# controller.net
KiCad netlist of a schematic drawn in EAGLE
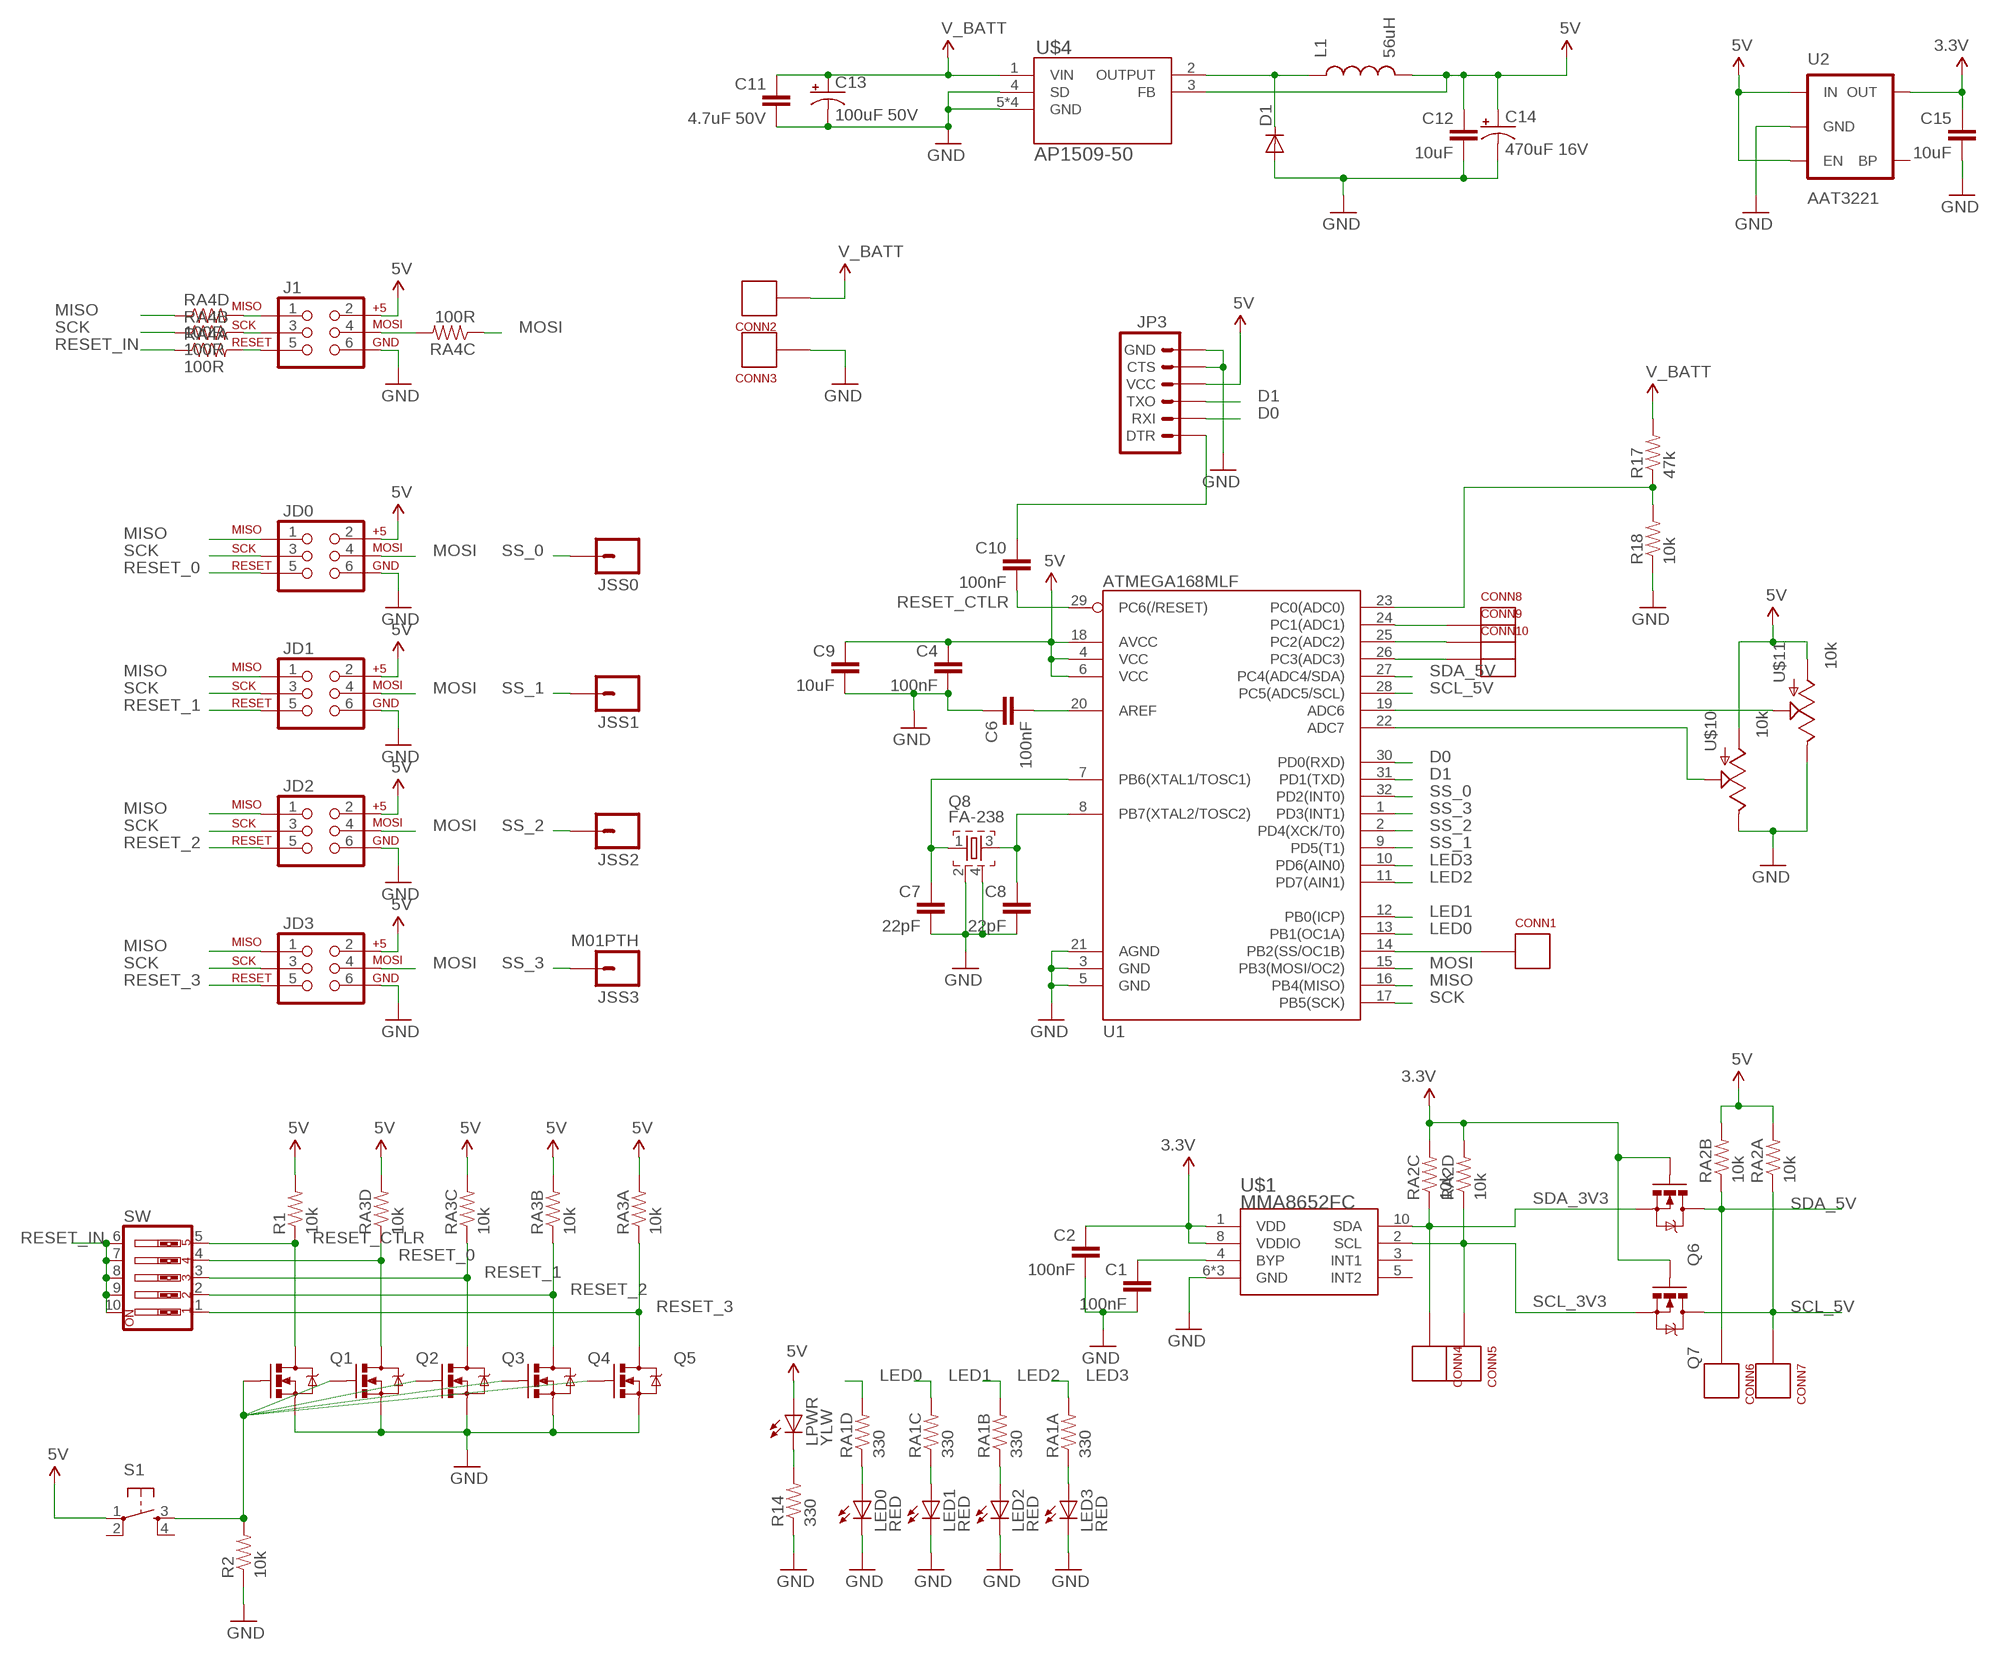
[diagram p0: schematic, sheet 1]

(export (version "E")
  (design (tool "Eeschema 10.0.6"))
  (components
    (comp (ref "C1")
      (value "100nF")
      (footprint "eagle-import:0402-CAP")
      (libsource (lib "eagle-import") (part "CAP0402-CAP"))
    )
    (comp (ref "C2")
      (value "100nF")
      (footprint "eagle-import:0402-CAP")
      (libsource (lib "eagle-import") (part "CAP0402-CAP"))
    )
    (comp (ref "C4")
      (value "100nF")
      (footprint "eagle-import:0402-CAP")
      (libsource (lib "eagle-import") (part "CAP0402-CAP"))
    )
    (comp (ref "C6")
      (value "100nF")
      (footprint "eagle-import:0402-CAP")
      (libsource (lib "eagle-import") (part "CAP0402-CAP"))
    )
    (comp (ref "C7")
      (value "22pF")
      (footprint "eagle-import:0402-CAP")
      (libsource (lib "eagle-import") (part "CAP0402-CAP"))
    )
    (comp (ref "C8")
      (value "22pF")
      (footprint "eagle-import:0402-CAP")
      (libsource (lib "eagle-import") (part "CAP0402-CAP"))
    )
    (comp (ref "C9")
      (value "10uF")
      (footprint "eagle-import:0805")
      (libsource (lib "eagle-import") (part "CAP0805"))
    )
    (comp (ref "C10")
      (value "100nF")
      (footprint "eagle-import:0402-CAP")
      (libsource (lib "eagle-import") (part "CAP0402-CAP"))
    )
    (comp (ref "C11")
      (value "4.7uF 50V")
      (footprint "eagle-import:0805")
      (libsource (lib "eagle-import") (part "CAP0805"))
    )
    (comp (ref "C12")
      (value "10uF")
      (footprint "eagle-import:0805")
      (libsource (lib "eagle-import") (part "CAP0805"))
    )
    (comp (ref "C13")
      (value "100uF 50V")
      (footprint "eagle-import:CAP-8-3.5")
      (libsource (lib "eagle-import") (part "CAP_POLPTH6"))
    )
    (comp (ref "C14")
      (value "470uF 16V")
      (footprint "eagle-import:CAP-8-3.5")
      (libsource (lib "eagle-import") (part "CAP_POLPTH6"))
    )
    (comp (ref "C15")
      (value "10uF")
      (footprint "eagle-import:0805")
      (libsource (lib "eagle-import") (part "CAP0805"))
    )
    (comp (ref "CONN1")
      (value "SS")
      (footprint "eagle-import:TESTPAD")
      (libsource (lib "eagle-import") (part "CONNECTOR"))
    )
    (comp (ref "CONN2")
      (value "CONNECTOR18AWG")
      (footprint "eagle-import:HOLE_18AWG")
      (libsource (lib "eagle-import") (part "CONNECTOR18AWG"))
    )
    (comp (ref "CONN3")
      (value "CONNECTOR18AWG")
      (footprint "eagle-import:HOLE_18AWG")
      (libsource (lib "eagle-import") (part "CONNECTOR18AWG"))
    )
    (comp (ref "CONN4")
      (value "D33")
      (footprint "eagle-import:TESTPAD")
      (libsource (lib "eagle-import") (part "CONNECTOR"))
    )
    (comp (ref "CONN5")
      (value "C33")
      (footprint "eagle-import:TESTPAD")
      (libsource (lib "eagle-import") (part "CONNECTOR"))
    )
    (comp (ref "CONN6")
      (value "D50")
      (footprint "eagle-import:TESTPAD")
      (libsource (lib "eagle-import") (part "CONNECTOR"))
    )
    (comp (ref "CONN7")
      (value "C50")
      (footprint "eagle-import:TESTPAD")
      (libsource (lib "eagle-import") (part "CONNECTOR"))
    )
    (comp (ref "CONN8")
      (value "PC1")
      (footprint "eagle-import:TESTPAD")
      (libsource (lib "eagle-import") (part "CONNECTOR"))
    )
    (comp (ref "CONN9")
      (value "PC2")
      (footprint "eagle-import:TESTPAD")
      (libsource (lib "eagle-import") (part "CONNECTOR"))
    )
    (comp (ref "CONN10")
      (value "PC3")
      (footprint "eagle-import:TESTPAD")
      (libsource (lib "eagle-import") (part "CONNECTOR"))
    )
    (comp (ref "D1")
      (value "DIODESOD123W")
      (footprint "eagle-import:SOD123W(NXP)")
      (libsource (lib "eagle-import") (part "DIODESOD123W"))
    )
    (comp (ref "J1")
      (value "AVR_SPI_PRG_6PTH")
      (footprint "eagle-import:2X3")
      (libsource (lib "eagle-import") (part "AVR_SPI_PRG_6PTH"))
    )
    (comp (ref "JD0")
      (value "AVR_SPI_PRG_6PTH")
      (footprint "eagle-import:2X3")
      (libsource (lib "eagle-import") (part "AVR_SPI_PRG_6PTH"))
    )
    (comp (ref "JD1")
      (value "AVR_SPI_PRG_6PTH")
      (footprint "eagle-import:2X3")
      (libsource (lib "eagle-import") (part "AVR_SPI_PRG_6PTH"))
    )
    (comp (ref "JD2")
      (value "AVR_SPI_PRG_6PTH")
      (footprint "eagle-import:2X3")
      (libsource (lib "eagle-import") (part "AVR_SPI_PRG_6PTH"))
    )
    (comp (ref "JD3")
      (value "AVR_SPI_PRG_6PTH")
      (footprint "eagle-import:2X3")
      (libsource (lib "eagle-import") (part "AVR_SPI_PRG_6PTH"))
    )
    (comp (ref "JP3")
      (value "ARDUINO_SERIAL_PROGRAMPTH")
      (footprint "eagle-import:1X06")
      (libsource (lib "eagle-import") (part "ARDUINO_SERIAL_PROGRAMPTH"))
    )
    (comp (ref "JSS0")
      (value "M01PTH")
      (footprint "eagle-import:1X01")
      (libsource (lib "eagle-import") (part "M01PTH"))
    )
    (comp (ref "JSS1")
      (value "M01PTH")
      (footprint "eagle-import:1X01")
      (libsource (lib "eagle-import") (part "M01PTH"))
    )
    (comp (ref "JSS2")
      (value "M01PTH")
      (footprint "eagle-import:1X01")
      (libsource (lib "eagle-import") (part "M01PTH"))
    )
    (comp (ref "JSS3")
      (value "M01PTH")
      (footprint "eagle-import:1X01")
      (libsource (lib "eagle-import") (part "M01PTH"))
    )
    (comp (ref "L1")
      (value "56uH")
      (footprint "eagle-import:1210")
      (libsource (lib "eagle-import") (part "INDUCTOR1210"))
    )
    (comp (ref "LED0")
      (value "RED")
      (footprint "eagle-import:LED-0603")
      (libsource (lib "eagle-import") (part "LED-RED0603"))
    )
    (comp (ref "LED1")
      (value "RED")
      (footprint "eagle-import:LED-0603")
      (libsource (lib "eagle-import") (part "LED-RED0603"))
    )
    (comp (ref "LED2")
      (value "RED")
      (footprint "eagle-import:LED-0603")
      (libsource (lib "eagle-import") (part "LED-RED0603"))
    )
    (comp (ref "LED3")
      (value "RED")
      (footprint "eagle-import:LED-0603")
      (libsource (lib "eagle-import") (part "LED-RED0603"))
    )
    (comp (ref "LPWR")
      (value "YLW")
      (footprint "eagle-import:LED-0603")
      (libsource (lib "eagle-import") (part "LED-RED0603"))
    )
    (comp (ref "Q1")
      (value "MOSFET-NCHANNELBSS123LT1G")
      (footprint "eagle-import:SOT23")
      (libsource (lib "eagle-import") (part "MOSFET-NCHANNELBSS123LT1G"))
    )
    (comp (ref "Q2")
      (value "MOSFET-NCHANNELBSS123LT1G")
      (footprint "eagle-import:SOT23")
      (libsource (lib "eagle-import") (part "MOSFET-NCHANNELBSS123LT1G"))
    )
    (comp (ref "Q3")
      (value "MOSFET-NCHANNELBSS123LT1G")
      (footprint "eagle-import:SOT23")
      (libsource (lib "eagle-import") (part "MOSFET-NCHANNELBSS123LT1G"))
    )
    (comp (ref "Q4")
      (value "MOSFET-NCHANNELBSS123LT1G")
      (footprint "eagle-import:SOT23")
      (libsource (lib "eagle-import") (part "MOSFET-NCHANNELBSS123LT1G"))
    )
    (comp (ref "Q5")
      (value "MOSFET-NCHANNELBSS123LT1G")
      (footprint "eagle-import:SOT23")
      (libsource (lib "eagle-import") (part "MOSFET-NCHANNELBSS123LT1G"))
    )
    (comp (ref "Q6")
      (value "MOSFET-NCHANNELBSS123LT1G")
      (footprint "eagle-import:SOT23")
      (libsource (lib "eagle-import") (part "MOSFET-NCHANNELBSS123LT1G"))
    )
    (comp (ref "Q7")
      (value "MOSFET-NCHANNELBSS123LT1G")
      (footprint "eagle-import:SOT23")
      (libsource (lib "eagle-import") (part "MOSFET-NCHANNELBSS123LT1G"))
    )
    (comp (ref "Q8")
      (value "FA-238")
      (footprint "eagle-import:FA-238")
      (libsource (lib "eagle-import") (part "FA-238"))
    )
    (comp (ref "R1")
      (value "10k")
      (footprint "eagle-import:0603-RES")
      (libsource (lib "eagle-import") (part "kmod_RESISTOR0603"))
    )
    (comp (ref "R2")
      (value "10k")
      (footprint "eagle-import:0603-RES")
      (libsource (lib "eagle-import") (part "kmod_RESISTOR0603"))
    )
    (comp (ref "R14")
      (value "330")
      (footprint "eagle-import:0603-RES")
      (libsource (lib "eagle-import") (part "RESISTOR0603"))
    )
    (comp (ref "R17")
      (value "47k")
      (footprint "eagle-import:0603-RES")
      (libsource (lib "eagle-import") (part "kmod_RESISTOR0603"))
    )
    (comp (ref "R18")
      (value "10k")
      (footprint "eagle-import:0603-RES")
      (libsource (lib "eagle-import") (part "kmod_RESISTOR0603"))
    )
    (comp (ref "RA1")
      (value "330")
      (footprint "eagle-import:0603-ARV")
      (libsource (lib "eagle-import") (part "RESISTOR_ARRAY0603_X4"))
    )
    (comp (ref "RA2")
      (value "10k")
      (footprint "eagle-import:0603-ARV")
      (libsource (lib "eagle-import") (part "RESISTOR_ARRAY0603_X4"))
    )
    (comp (ref "RA3")
      (value "10k")
      (footprint "eagle-import:0603-ARV")
      (libsource (lib "eagle-import") (part "RESISTOR_ARRAY0603_X4"))
    )
    (comp (ref "RA4")
      (value "100R")
      (footprint "eagle-import:0603-ARV")
      (libsource (lib "eagle-import") (part "RESISTOR_ARRAY0603_X4"))
    )
    (comp (ref "S1")
      (value "TAC_SWITCHPTH")
      (footprint "eagle-import:TACTILE-PTH")
      (libsource (lib "eagle-import") (part "TAC_SWITCHPTH"))
    )
    (comp (ref "SW")
      (value "SW_DIP-5")
      (footprint "eagle-import:DIPSWITCH-05")
      (libsource (lib "eagle-import") (part "SW_DIP-5"))
    )
    (comp (ref "U$1")
      (value "MMA8652FC")
      (footprint "eagle-import:DFN-10")
      (libsource (lib "eagle-import") (part "MMA8652FC"))
    )
    (comp (ref "U$4")
      (value "AP1509-50")
      (footprint "eagle-import:SO08")
      (libsource (lib "eagle-import") (part "AP1509"))
    )
    (comp (ref "U$10")
      (value "10k")
      (footprint "eagle-import:TRIM_POT")
      (libsource (lib "eagle-import") (part "POTTRIM"))
    )
    (comp (ref "U$11")
      (value "10k")
      (footprint "eagle-import:TRIM_POT")
      (libsource (lib "eagle-import") (part "POTTRIM"))
    )
    (comp (ref "U1")
      (value "ATMEGA168MLF")
      (footprint "eagle-import:MLF32")
      (libsource (lib "eagle-import") (part "ATMEGA168MLF"))
    )
    (comp (ref "U2")
      (value "AAT3221")
      (footprint "eagle-import:SOT23-5")
      (libsource (lib "eagle-import") (part "V_REG_LDOSMD"))
    )
  )
  (nets
    (net (code "1") (name "/D0") (class "Default")
      (node (ref "JP3") (pin "2") (pinfunction "RXI_2") (pintype "passive"))
      (node (ref "U1") (pin "30") (pinfunction "PD0(RXD)_30") (pintype "bidirectional"))
    )
    (net (code "2") (name "/D1") (class "Default")
      (node (ref "JP3") (pin "3") (pinfunction "TXO_3") (pintype "passive"))
      (node (ref "U1") (pin "31") (pinfunction "PD1(TXD)_31") (pintype "bidirectional"))
    )
    (net (code "3") (name "/LED0") (class "Default")
      (node (ref "RA1") (pin "5") (pinfunction "2_5") (pintype "passive"))
      (node (ref "U1") (pin "13") (pinfunction "PB1(OC1A)_13") (pintype "bidirectional"))
    )
    (net (code "4") (name "/LED1") (class "Default")
      (node (ref "RA1") (pin "6") (pinfunction "2_6") (pintype "passive"))
      (node (ref "U1") (pin "12") (pinfunction "PB0(ICP)_12") (pintype "bidirectional"))
    )
    (net (code "5") (name "/LED2") (class "Default")
      (node (ref "RA1") (pin "7") (pinfunction "2_7") (pintype "passive"))
      (node (ref "U1") (pin "11") (pinfunction "PD7(AIN1)_11") (pintype "bidirectional"))
    )
    (net (code "6") (name "/LED3") (class "Default")
      (node (ref "RA1") (pin "8") (pinfunction "2_8") (pintype "passive"))
      (node (ref "U1") (pin "10") (pinfunction "PD6(AIN0)_10") (pintype "bidirectional"))
    )
    (net (code "7") (name "/MISO") (class "Default")
      (node (ref "JD0") (pin "1") (pinfunction "1_1") (pintype "passive"))
      (node (ref "JD1") (pin "1") (pinfunction "1_1") (pintype "passive"))
      (node (ref "JD2") (pin "1") (pinfunction "1_1") (pintype "passive"))
      (node (ref "JD3") (pin "1") (pinfunction "1_1") (pintype "passive"))
      (node (ref "RA4") (pin "4") (pinfunction "1_4") (pintype "passive"))
      (node (ref "U1") (pin "16") (pinfunction "PB4(MISO)_16") (pintype "bidirectional"))
    )
    (net (code "8") (name "/MOSI") (class "Default")
      (node (ref "JD0") (pin "4") (pinfunction "4_4") (pintype "passive"))
      (node (ref "JD1") (pin "4") (pinfunction "4_4") (pintype "passive"))
      (node (ref "JD2") (pin "4") (pinfunction "4_4") (pintype "passive"))
      (node (ref "JD3") (pin "4") (pinfunction "4_4") (pintype "passive"))
      (node (ref "RA4") (pin "3") (pinfunction "1_3") (pintype "passive"))
      (node (ref "U1") (pin "15") (pinfunction "PB3(MOSI/OC2)_15") (pintype "bidirectional"))
    )
    (net (code "9") (name "/RESET_0") (class "Default")
      (node (ref "JD0") (pin "5") (pinfunction "5_5") (pintype "passive"))
      (node (ref "Q2") (pin "3") (pinfunction "D_3") (pintype "passive"))
      (node (ref "RA3") (pin "4") (pinfunction "1_4") (pintype "passive"))
      (node (ref "SW") (pin "4") (pinfunction "4_4") (pintype "passive"))
    )
    (net (code "10") (name "/RESET_1") (class "Default")
      (node (ref "JD1") (pin "5") (pinfunction "5_5") (pintype "passive"))
      (node (ref "Q3") (pin "3") (pinfunction "D_3") (pintype "passive"))
      (node (ref "RA3") (pin "3") (pinfunction "1_3") (pintype "passive"))
      (node (ref "SW") (pin "3") (pinfunction "3_3") (pintype "passive"))
    )
    (net (code "11") (name "/RESET_2") (class "Default")
      (node (ref "JD2") (pin "5") (pinfunction "5_5") (pintype "passive"))
      (node (ref "Q4") (pin "3") (pinfunction "D_3") (pintype "passive"))
      (node (ref "RA3") (pin "2") (pinfunction "1_2") (pintype "passive"))
      (node (ref "SW") (pin "2") (pinfunction "2_2") (pintype "passive"))
    )
    (net (code "12") (name "/RESET_3") (class "Default")
      (node (ref "JD3") (pin "5") (pinfunction "5_5") (pintype "passive"))
      (node (ref "Q5") (pin "3") (pinfunction "D_3") (pintype "passive"))
      (node (ref "RA3") (pin "1") (pinfunction "1_1") (pintype "passive"))
      (node (ref "SW") (pin "1") (pinfunction "1_1") (pintype "passive"))
    )
    (net (code "13") (name "/RESET_CTLR") (class "Default")
      (node (ref "C10") (pin "2") (pinfunction "2_2") (pintype "passive"))
      (node (ref "Q1") (pin "3") (pinfunction "D_3") (pintype "passive"))
      (node (ref "R1") (pin "1") (pinfunction "1_1") (pintype "passive"))
      (node (ref "SW") (pin "5") (pinfunction "5_5") (pintype "passive"))
      (node (ref "U1") (pin "29") (pinfunction "PC6(/RESET)_29") (pintype "bidirectional"))
    )
    (net (code "14") (name "/RESET_IN") (class "Default")
      (node (ref "RA4") (pin "1") (pinfunction "1_1") (pintype "passive"))
      (node (ref "SW") (pin "10") (pinfunction "16_10") (pintype "passive"))
      (node (ref "SW") (pin "6") (pinfunction "12_6") (pintype "passive"))
      (node (ref "SW") (pin "7") (pinfunction "13_7") (pintype "passive"))
      (node (ref "SW") (pin "8") (pinfunction "14_8") (pintype "passive"))
      (node (ref "SW") (pin "9") (pinfunction "15_9") (pintype "passive"))
    )
    (net (code "15") (name "/SCK") (class "Default")
      (node (ref "JD0") (pin "3") (pinfunction "3_3") (pintype "passive"))
      (node (ref "JD1") (pin "3") (pinfunction "3_3") (pintype "passive"))
      (node (ref "JD2") (pin "3") (pinfunction "3_3") (pintype "passive"))
      (node (ref "JD3") (pin "3") (pinfunction "3_3") (pintype "passive"))
      (node (ref "RA4") (pin "2") (pinfunction "1_2") (pintype "passive"))
      (node (ref "U1") (pin "17") (pinfunction "PB5(SCK)_17") (pintype "bidirectional"))
    )
    (net (code "16") (name "/SCL_3V3") (class "Default")
      (node (ref "CONN5") (pin "P") (pinfunction "P_P") (pintype "bidirectional"))
      (node (ref "Q7") (pin "2") (pinfunction "S_2") (pintype "passive"))
      (node (ref "RA2") (pin "4") (pinfunction "1_4") (pintype "passive"))
      (node (ref "U$1") (pin "2") (pinfunction "SCL_2") (pintype "bidirectional"))
    )
    (net (code "17") (name "/SCL_5V") (class "Default")
      (node (ref "CONN7") (pin "P") (pinfunction "P_P") (pintype "bidirectional"))
      (node (ref "Q7") (pin "3") (pinfunction "D_3") (pintype "passive"))
      (node (ref "RA2") (pin "1") (pinfunction "1_1") (pintype "passive"))
      (node (ref "U1") (pin "28") (pinfunction "PC5(ADC5/SCL)_28") (pintype "bidirectional"))
    )
    (net (code "18") (name "/SDA_3V3") (class "Default")
      (node (ref "CONN4") (pin "P") (pinfunction "P_P") (pintype "bidirectional"))
      (node (ref "Q6") (pin "2") (pinfunction "S_2") (pintype "passive"))
      (node (ref "RA2") (pin "3") (pinfunction "1_3") (pintype "passive"))
      (node (ref "U$1") (pin "10") (pinfunction "SDA_10") (pintype "bidirectional"))
    )
    (net (code "19") (name "/SDA_5V") (class "Default")
      (node (ref "CONN6") (pin "P") (pinfunction "P_P") (pintype "bidirectional"))
      (node (ref "Q6") (pin "3") (pinfunction "D_3") (pintype "passive"))
      (node (ref "RA2") (pin "2") (pinfunction "1_2") (pintype "passive"))
      (node (ref "U1") (pin "27") (pinfunction "PC4(ADC4/SDA)_27") (pintype "bidirectional"))
    )
    (net (code "20") (name "/SS_0") (class "Default")
      (node (ref "JSS0") (pin "1") (pinfunction "1_1") (pintype "passive"))
      (node (ref "U1") (pin "32") (pinfunction "PD2(INT0)_32") (pintype "bidirectional"))
    )
    (net (code "21") (name "/SS_1") (class "Default")
      (node (ref "JSS1") (pin "1") (pinfunction "1_1") (pintype "passive"))
      (node (ref "U1") (pin "9") (pinfunction "PD5(T1)_9") (pintype "bidirectional"))
    )
    (net (code "22") (name "/SS_2") (class "Default")
      (node (ref "JSS2") (pin "1") (pinfunction "1_1") (pintype "passive"))
      (node (ref "U1") (pin "2") (pinfunction "PD4(XCK/T0)_2") (pintype "bidirectional"))
    )
    (net (code "23") (name "/SS_3") (class "Default")
      (node (ref "JSS3") (pin "1") (pinfunction "1_1") (pintype "passive"))
      (node (ref "U1") (pin "1") (pinfunction "PD3(INT1)_1") (pintype "bidirectional"))
    )
    (net (code "24") (name "3.3V") (class "Default")
      (node (ref "C15") (pin "1") (pinfunction "1_1") (pintype "passive"))
      (node (ref "C2") (pin "1") (pinfunction "1_1") (pintype "passive"))
      (node (ref "Q6") (pin "1") (pinfunction "G_1") (pintype "passive"))
      (node (ref "Q7") (pin "1") (pinfunction "G_1") (pintype "passive"))
      (node (ref "RA2") (pin "5") (pinfunction "2_5") (pintype "passive"))
      (node (ref "RA2") (pin "6") (pinfunction "2_6") (pintype "passive"))
      (node (ref "U$1") (pin "1") (pinfunction "VDD_1") (pintype "bidirectional"))
      (node (ref "U$1") (pin "8") (pinfunction "VDDIO_8") (pintype "bidirectional"))
      (node (ref "U2") (pin "5") (pinfunction "OUT_5") (pintype "passive"))
    )
    (net (code "25") (name "5V") (class "Default")
      (node (ref "C12") (pin "1") (pinfunction "1_1") (pintype "passive"))
      (node (ref "C14") (pin "1") (pinfunction "+_1") (pintype "passive"))
      (node (ref "C4") (pin "1") (pinfunction "1_1") (pintype "passive"))
      (node (ref "C9") (pin "1") (pinfunction "1_1") (pintype "passive"))
      (node (ref "J1") (pin "2") (pinfunction "2_2") (pintype "passive"))
      (node (ref "JD0") (pin "2") (pinfunction "2_2") (pintype "passive"))
      (node (ref "JD1") (pin "2") (pinfunction "2_2") (pintype "passive"))
      (node (ref "JD2") (pin "2") (pinfunction "2_2") (pintype "passive"))
      (node (ref "JD3") (pin "2") (pinfunction "2_2") (pintype "passive"))
      (node (ref "JP3") (pin "4") (pinfunction "VCC_4") (pintype "passive"))
      (node (ref "L1") (pin "2") (pinfunction "2_2") (pintype "passive"))
      (node (ref "LPWR") (pin "A") (pinfunction "A_A") (pintype "passive"))
      (node (ref "R1") (pin "2") (pinfunction "2_2") (pintype "passive"))
      (node (ref "RA2") (pin "7") (pinfunction "2_7") (pintype "passive"))
      (node (ref "RA2") (pin "8") (pinfunction "2_8") (pintype "passive"))
      (node (ref "RA3") (pin "5") (pinfunction "2_5") (pintype "passive"))
      (node (ref "RA3") (pin "6") (pinfunction "2_6") (pintype "passive"))
      (node (ref "RA3") (pin "7") (pinfunction "2_7") (pintype "passive"))
      (node (ref "RA3") (pin "8") (pinfunction "2_8") (pintype "passive"))
      (node (ref "S1") (pin "1") (pinfunction "1_1") (pintype "passive"))
      (node (ref "U$10") (pin "3") (pinfunction "A_3") (pintype "passive"))
      (node (ref "U$11") (pin "3") (pinfunction "A_3") (pintype "passive"))
      (node (ref "U$4") (pin "3") (pinfunction "FB_3") (pintype "bidirectional"))
      (node (ref "U1") (pin "18") (pinfunction "AVCC_18") (pintype "bidirectional"))
      (node (ref "U1") (pin "4") (pinfunction "VCC_4") (pintype "bidirectional"))
      (node (ref "U1") (pin "6") (pinfunction "VCC_6") (pintype "bidirectional"))
      (node (ref "U2") (pin "1") (pinfunction "IN_1") (pintype "input"))
      (node (ref "U2") (pin "3") (pinfunction "EN_3") (pintype "input"))
    )
    (net (code "26") (name "GND") (class "Default")
      (node (ref "C1") (pin "2") (pinfunction "2_2") (pintype "passive"))
      (node (ref "C11") (pin "2") (pinfunction "2_2") (pintype "passive"))
      (node (ref "C12") (pin "2") (pinfunction "2_2") (pintype "passive"))
      (node (ref "C13") (pin "2") (pinfunction "-_2") (pintype "passive"))
      (node (ref "C14") (pin "2") (pinfunction "-_2") (pintype "passive"))
      (node (ref "C15") (pin "2") (pinfunction "2_2") (pintype "passive"))
      (node (ref "C2") (pin "2") (pinfunction "2_2") (pintype "passive"))
      (node (ref "C4") (pin "2") (pinfunction "2_2") (pintype "passive"))
      (node (ref "C6") (pin "1") (pinfunction "1_1") (pintype "passive"))
      (node (ref "C7") (pin "2") (pinfunction "2_2") (pintype "passive"))
      (node (ref "C8") (pin "2") (pinfunction "2_2") (pintype "passive"))
      (node (ref "C9") (pin "2") (pinfunction "2_2") (pintype "passive"))
      (node (ref "CONN3") (pin "P$1") (pinfunction "P_P$1") (pintype "bidirectional"))
      (node (ref "D1") (pin "A") (pinfunction "A_A") (pintype "passive"))
      (node (ref "J1") (pin "6") (pinfunction "6_6") (pintype "passive"))
      (node (ref "JD0") (pin "6") (pinfunction "6_6") (pintype "passive"))
      (node (ref "JD1") (pin "6") (pinfunction "6_6") (pintype "passive"))
      (node (ref "JD2") (pin "6") (pinfunction "6_6") (pintype "passive"))
      (node (ref "JD3") (pin "6") (pinfunction "6_6") (pintype "passive"))
      (node (ref "JP3") (pin "5") (pinfunction "CTS_5") (pintype "passive"))
      (node (ref "JP3") (pin "6") (pinfunction "GND_6") (pintype "passive"))
      (node (ref "LED0") (pin "C") (pinfunction "C_C") (pintype "passive"))
      (node (ref "LED1") (pin "C") (pinfunction "C_C") (pintype "passive"))
      (node (ref "LED2") (pin "C") (pinfunction "C_C") (pintype "passive"))
      (node (ref "LED3") (pin "C") (pinfunction "C_C") (pintype "passive"))
      (node (ref "Q1") (pin "2") (pinfunction "S_2") (pintype "passive"))
      (node (ref "Q2") (pin "2") (pinfunction "S_2") (pintype "passive"))
      (node (ref "Q3") (pin "2") (pinfunction "S_2") (pintype "passive"))
      (node (ref "Q4") (pin "2") (pinfunction "S_2") (pintype "passive"))
      (node (ref "Q5") (pin "2") (pinfunction "S_2") (pintype "passive"))
      (node (ref "Q8") (pin "2") (pinfunction "2_2") (pintype "passive"))
      (node (ref "Q8") (pin "4") (pinfunction "4_4") (pintype "passive"))
      (node (ref "R14") (pin "1") (pinfunction "1_1") (pintype "passive"))
      (node (ref "R18") (pin "1") (pinfunction "1_1") (pintype "passive"))
      (node (ref "R2") (pin "1") (pinfunction "1_1") (pintype "passive"))
      (node (ref "U$1") (pin "6") (pinfunction "GND_6") (pintype "bidirectional"))
      (node (ref "U$1") (pin "7") (pinfunction "GND_7") (pintype "bidirectional"))
      (node (ref "U$1") (pin "9") (pinfunction "GND_9") (pintype "bidirectional"))
      (node (ref "U$10") (pin "2") (pinfunction "E_2") (pintype "passive"))
      (node (ref "U$11") (pin "2") (pinfunction "E_2") (pintype "passive"))
      (node (ref "U$4") (pin "4") (pinfunction "SD_4") (pintype "bidirectional"))
      (node (ref "U$4") (pin "5") (pinfunction "GND_5") (pintype "bidirectional"))
      (node (ref "U$4") (pin "6") (pinfunction "GND_6") (pintype "bidirectional"))
      (node (ref "U$4") (pin "7") (pinfunction "GND_7") (pintype "bidirectional"))
      (node (ref "U$4") (pin "8") (pinfunction "GND_8") (pintype "bidirectional"))
      (node (ref "U1") (pin "21") (pinfunction "AGND_21") (pintype "bidirectional"))
      (node (ref "U1") (pin "3") (pinfunction "GND_3") (pintype "bidirectional"))
      (node (ref "U1") (pin "5") (pinfunction "GND_5") (pintype "bidirectional"))
      (node (ref "U2") (pin "2") (pinfunction "GND_2") (pintype "input"))
    )
    (net (code "27") (name "Net-(JP3-DTR)") (class "Default")
      (node (ref "C10") (pin "1") (pinfunction "1_1") (pintype "passive"))
      (node (ref "JP3") (pin "1") (pinfunction "DTR_1") (pintype "passive"))
    )
    (net (code "28") (name "Net-(LED3-PadA)") (class "Default")
      (node (ref "LED3") (pin "A") (pinfunction "A_A") (pintype "passive"))
      (node (ref "RA1") (pin "1") (pinfunction "1_1") (pintype "passive"))
    )
    (net (code "29") (name "Net-(LPWR-PadC)") (class "Default")
      (node (ref "LPWR") (pin "C") (pinfunction "C_C") (pintype "passive"))
      (node (ref "R14") (pin "2") (pinfunction "2_2") (pintype "passive"))
    )
    (net (code "30") (name "Net-(Q1-G)") (class "Default")
      (node (ref "Q1") (pin "1") (pinfunction "G_1") (pintype "passive"))
      (node (ref "Q2") (pin "1") (pinfunction "G_1") (pintype "passive"))
      (node (ref "Q3") (pin "1") (pinfunction "G_1") (pintype "passive"))
      (node (ref "Q4") (pin "1") (pinfunction "G_1") (pintype "passive"))
      (node (ref "Q5") (pin "1") (pinfunction "G_1") (pintype "passive"))
      (node (ref "R2") (pin "2") (pinfunction "2_2") (pintype "passive"))
      (node (ref "S1") (pin "3") (pinfunction "3_3") (pintype "passive"))
    )
    (net (code "31") (name "Net-(RA1B-1)") (class "Default")
      (node (ref "LED2") (pin "A") (pinfunction "A_A") (pintype "passive"))
      (node (ref "RA1") (pin "2") (pinfunction "1_2") (pintype "passive"))
    )
    (net (code "32") (name "Net-(RA1C-1)") (class "Default")
      (node (ref "LED1") (pin "A") (pinfunction "A_A") (pintype "passive"))
      (node (ref "RA1") (pin "3") (pinfunction "1_3") (pintype "passive"))
    )
    (net (code "33") (name "Net-(RA1D-1)") (class "Default")
      (node (ref "LED0") (pin "A") (pinfunction "A_A") (pintype "passive"))
      (node (ref "RA1") (pin "4") (pinfunction "1_4") (pintype "passive"))
    )
    (net (code "34") (name "Net-(RA4A-2)") (class "Default")
      (node (ref "J1") (pin "5") (pinfunction "5_5") (pintype "passive"))
      (node (ref "RA4") (pin "8") (pinfunction "2_8") (pintype "passive"))
    )
    (net (code "35") (name "Net-(RA4B-2)") (class "Default")
      (node (ref "J1") (pin "3") (pinfunction "3_3") (pintype "passive"))
      (node (ref "RA4") (pin "7") (pinfunction "2_7") (pintype "passive"))
    )
    (net (code "36") (name "Net-(RA4C-2)") (class "Default")
      (node (ref "J1") (pin "4") (pinfunction "4_4") (pintype "passive"))
      (node (ref "RA4") (pin "6") (pinfunction "2_6") (pintype "passive"))
    )
    (net (code "37") (name "Net-(RA4D-2)") (class "Default")
      (node (ref "J1") (pin "1") (pinfunction "1_1") (pintype "passive"))
      (node (ref "RA4") (pin "5") (pinfunction "2_5") (pintype "passive"))
    )
    (net (code "38") (name "Net-(U$1-BYP)") (class "Default")
      (node (ref "C1") (pin "1") (pinfunction "1_1") (pintype "passive"))
      (node (ref "U$1") (pin "4") (pinfunction "BYP_4") (pintype "bidirectional"))
    )
    (net (code "39") (name "Net-(U$4-OUTPUT)") (class "Default")
      (node (ref "D1") (pin "C") (pinfunction "C_C") (pintype "passive"))
      (node (ref "L1") (pin "1") (pinfunction "1_1") (pintype "passive"))
      (node (ref "U$4") (pin "2") (pinfunction "OUTPUT_2") (pintype "bidirectional"))
    )
    (net (code "40") (name "Net-(U$10-S)") (class "Default")
      (node (ref "U$10") (pin "1") (pinfunction "S_1") (pintype "passive"))
      (node (ref "U1") (pin "22") (pinfunction "ADC7_22") (pintype "bidirectional"))
    )
    (net (code "41") (name "Net-(U$11-S)") (class "Default")
      (node (ref "U$11") (pin "1") (pinfunction "S_1") (pintype "passive"))
      (node (ref "U1") (pin "19") (pinfunction "ADC6_19") (pintype "bidirectional"))
    )
    (net (code "42") (name "Net-(U1-AREF)") (class "Default")
      (node (ref "C6") (pin "2") (pinfunction "2_2") (pintype "passive"))
      (node (ref "U1") (pin "20") (pinfunction "AREF_20") (pintype "bidirectional"))
    )
    (net (code "43") (name "Net-(U1-PB2(SS{slash}OC1B))") (class "Default")
      (node (ref "CONN1") (pin "P") (pinfunction "P_P") (pintype "bidirectional"))
      (node (ref "U1") (pin "14") (pinfunction "PB2(SS/OC1B)_14") (pintype "bidirectional"))
    )
    (net (code "44") (name "Net-(U1-PB6(XTAL1{slash}TOSC1))") (class "Default")
      (node (ref "C7") (pin "1") (pinfunction "1_1") (pintype "passive"))
      (node (ref "Q8") (pin "1") (pinfunction "1_1") (pintype "passive"))
      (node (ref "U1") (pin "7") (pinfunction "PB6(XTAL1/TOSC1)_7") (pintype "bidirectional"))
    )
    (net (code "45") (name "Net-(U1-PB7(XTAL2{slash}TOSC2))") (class "Default")
      (node (ref "C8") (pin "1") (pinfunction "1_1") (pintype "passive"))
      (node (ref "Q8") (pin "3") (pinfunction "3_3") (pintype "passive"))
      (node (ref "U1") (pin "8") (pinfunction "PB7(XTAL2/TOSC2)_8") (pintype "bidirectional"))
    )
    (net (code "46") (name "Net-(U1-PC0(ADC0))") (class "Default")
      (node (ref "R17") (pin "1") (pinfunction "1_1") (pintype "passive"))
      (node (ref "R18") (pin "2") (pinfunction "2_2") (pintype "passive"))
      (node (ref "U1") (pin "23") (pinfunction "PC0(ADC0)_23") (pintype "bidirectional"))
    )
    (net (code "47") (name "Net-(U1-PC1(ADC1))") (class "Default")
      (node (ref "CONN8") (pin "P") (pinfunction "P_P") (pintype "bidirectional"))
      (node (ref "U1") (pin "24") (pinfunction "PC1(ADC1)_24") (pintype "bidirectional"))
    )
    (net (code "48") (name "Net-(U1-PC2(ADC2))") (class "Default")
      (node (ref "CONN9") (pin "P") (pinfunction "P_P") (pintype "bidirectional"))
      (node (ref "U1") (pin "25") (pinfunction "PC2(ADC2)_25") (pintype "bidirectional"))
    )
    (net (code "49") (name "Net-(U1-PC3(ADC3))") (class "Default")
      (node (ref "CONN10") (pin "P") (pinfunction "P_P") (pintype "bidirectional"))
      (node (ref "U1") (pin "26") (pinfunction "PC3(ADC3)_26") (pintype "bidirectional"))
    )
    (net (code "50") (name "V_BATT") (class "Default")
      (node (ref "C11") (pin "1") (pinfunction "1_1") (pintype "passive"))
      (node (ref "C13") (pin "1") (pinfunction "+_1") (pintype "passive"))
      (node (ref "CONN2") (pin "P$1") (pinfunction "P_P$1") (pintype "bidirectional"))
      (node (ref "R17") (pin "2") (pinfunction "2_2") (pintype "passive"))
      (node (ref "U$4") (pin "1") (pinfunction "VIN_1") (pintype "bidirectional"))
    )
    (net (code "51") (name "unconnected-(S1-Pad2)") (class "Default")
      (node (ref "S1") (pin "2") (pinfunction "2_2") (pintype "passive"))
    )
    (net (code "52") (name "unconnected-(S1-Pad4)") (class "Default")
      (node (ref "S1") (pin "4") (pinfunction "4_4") (pintype "passive"))
    )
    (net (code "53") (name "unconnected-(U$1-INT1-Pad3)") (class "Default")
      (node (ref "U$1") (pin "3") (pinfunction "INT1_3") (pintype "bidirectional"))
    )
    (net (code "54") (name "unconnected-(U$1-INT2-Pad5)") (class "Default")
      (node (ref "U$1") (pin "5") (pinfunction "INT2_5") (pintype "bidirectional"))
    )
    (net (code "55") (name "unconnected-(U2-BP-Pad4)") (class "Default")
      (node (ref "U2") (pin "4") (pinfunction "BP_4") (pintype "input"))
    )
  )
)
